# Rev0.net
KiCad netlist of a schematic drawn in EAGLE
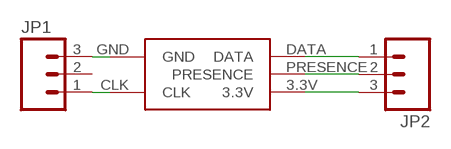
[diagram p0: schematic, sheet 1]

(export (version "E")
  (design (tool "Eeschema 10.0.6"))
  (components
    (comp (ref "JP1")
      (value "M03PTH")
      (footprint "eagle-import:1X03")
      (libsource (lib "eagle-import") (part "M03PTH"))
    )
    (comp (ref "JP2")
      (value "M03PTH")
      (footprint "eagle-import:1X03")
      (libsource (lib "eagle-import") (part "M03PTH"))
    )
    (comp (ref "U$1")
      (value "NUNCHUCK")
      (footprint "eagle-import:NUNCHUCK-SIMPLE")
      (libsource (lib "eagle-import") (part "NUNCHUCK"))
    )
  )
  (nets
    (net (code "1") (name "Net-(JP1-Pad1)") (class "Default")
      (node (ref "JP1") (pin "1") (pinfunction "1_1") (pintype "passive"))
      (node (ref "U$1") (pin "CLK") (pinfunction "CLK_CLK") (pintype "bidirectional"))
    )
    (net (code "2") (name "Net-(JP1-Pad3)") (class "Default")
      (node (ref "JP1") (pin "3") (pinfunction "3_3") (pintype "passive"))
      (node (ref "U$1") (pin "GND") (pinfunction "GND_GND") (pintype "bidirectional"))
    )
    (net (code "3") (name "Net-(JP2-Pad1)") (class "Default")
      (node (ref "JP2") (pin "1") (pinfunction "1_1") (pintype "passive"))
      (node (ref "U$1") (pin "DATA") (pinfunction "DATA_DATA") (pintype "bidirectional"))
    )
    (net (code "4") (name "Net-(JP2-Pad2)") (class "Default")
      (node (ref "JP2") (pin "2") (pinfunction "2_2") (pintype "passive"))
      (node (ref "U$1") (pin "PRESENCE") (pinfunction "PRESENCE_PRESENCE") (pintype "bidirectional"))
    )
    (net (code "5") (name "Net-(JP2-Pad3)") (class "Default")
      (node (ref "JP2") (pin "3") (pinfunction "3_3") (pintype "passive"))
      (node (ref "U$1") (pin "3.3V") (pinfunction "3.3V_3.3V") (pintype "bidirectional"))
    )
    (net (code "6") (name "unconnected-(JP1-Pad2)") (class "Default")
      (node (ref "JP1") (pin "2") (pinfunction "2_2") (pintype "passive"))
    )
  )
)
